# Trafic_led.net
KiCad netlist of a schematic drawn in EAGLE
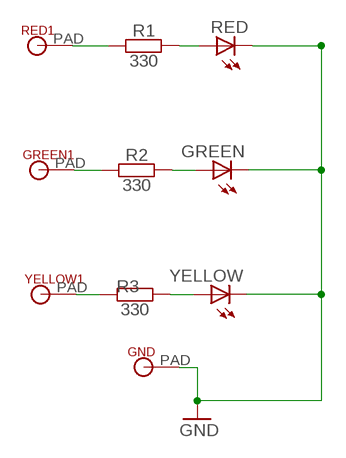
[diagram p0: schematic, sheet 1]

(export (version "E")
  (design (tool "Eeschema 10.0.6"))
  (components
    (comp (ref "GND")
      (value "MICROBIT_PAD")
      (footprint "eagle-import:MICROBIT_PAD")
      (libsource (lib "eagle-import") (part "MICROBIT_PAD"))
    )
    (comp (ref "GREEN")
      (value "LED3MM")
      (footprint "eagle-import:LED3MM")
      (libsource (lib "eagle-import") (part "LED3MM"))
    )
    (comp (ref "GREEN1")
      (value "MICROBIT_PAD")
      (footprint "eagle-import:MICROBIT_PAD")
      (libsource (lib "eagle-import") (part "MICROBIT_PAD"))
    )
    (comp (ref "R1")
      (value "330")
      (footprint "eagle-import:R0207_7")
      (libsource (lib "eagle-import") (part "RESISTOR-07"))
    )
    (comp (ref "R2")
      (value "330")
      (footprint "eagle-import:R0207_7")
      (libsource (lib "eagle-import") (part "RESISTOR-07"))
    )
    (comp (ref "R3")
      (value "330")
      (footprint "eagle-import:R0207_7")
      (libsource (lib "eagle-import") (part "RESISTOR-07"))
    )
    (comp (ref "RED")
      (value "LED3MM")
      (footprint "eagle-import:LED3MM")
      (libsource (lib "eagle-import") (part "LED3MM"))
    )
    (comp (ref "RED1")
      (value "MICROBIT_PAD")
      (footprint "eagle-import:MICROBIT_PAD")
      (libsource (lib "eagle-import") (part "MICROBIT_PAD"))
    )
    (comp (ref "YELLOW")
      (value "LED3MM")
      (footprint "eagle-import:LED3MM")
      (libsource (lib "eagle-import") (part "LED3MM"))
    )
    (comp (ref "YELLOW1")
      (value "MICROBIT_PAD")
      (footprint "eagle-import:MICROBIT_PAD")
      (libsource (lib "eagle-import") (part "MICROBIT_PAD"))
    )
  )
  (nets
    (net (code "1") (name "GND") (class "Default")
      (node (ref "GND") (pin "PAD") (pinfunction "P$1_PAD") (pintype "bidirectional"))
      (node (ref "GREEN") (pin "K") (pinfunction "C_K") (pintype "passive"))
      (node (ref "RED") (pin "K") (pinfunction "C_K") (pintype "passive"))
      (node (ref "YELLOW") (pin "K") (pinfunction "C_K") (pintype "passive"))
    )
    (net (code "2") (name "Net-(GREEN-PadA)") (class "Default")
      (node (ref "GREEN") (pin "A") (pinfunction "A_A") (pintype "passive"))
      (node (ref "R2") (pin "2") (pinfunction "2_2") (pintype "passive"))
    )
    (net (code "3") (name "Net-(GREEN1-P$1)") (class "Default")
      (node (ref "GREEN1") (pin "PAD") (pinfunction "P$1_PAD") (pintype "bidirectional"))
      (node (ref "R2") (pin "1") (pinfunction "1_1") (pintype "passive"))
    )
    (net (code "4") (name "Net-(R1-Pad2)") (class "Default")
      (node (ref "R1") (pin "2") (pinfunction "2_2") (pintype "passive"))
      (node (ref "RED") (pin "A") (pinfunction "A_A") (pintype "passive"))
    )
    (net (code "5") (name "Net-(R3-Pad2)") (class "Default")
      (node (ref "R3") (pin "2") (pinfunction "2_2") (pintype "passive"))
      (node (ref "YELLOW") (pin "A") (pinfunction "A_A") (pintype "passive"))
    )
    (net (code "6") (name "Net-(RED1-P$1)") (class "Default")
      (node (ref "R1") (pin "1") (pinfunction "1_1") (pintype "passive"))
      (node (ref "RED1") (pin "PAD") (pinfunction "P$1_PAD") (pintype "bidirectional"))
    )
    (net (code "7") (name "Net-(YELLOW1-P$1)") (class "Default")
      (node (ref "R3") (pin "1") (pinfunction "1_1") (pintype "passive"))
      (node (ref "YELLOW1") (pin "PAD") (pinfunction "P$1_PAD") (pintype "bidirectional"))
    )
  )
)
